# eth_part.net
KiCad netlist of a schematic drawn in Altium Designer
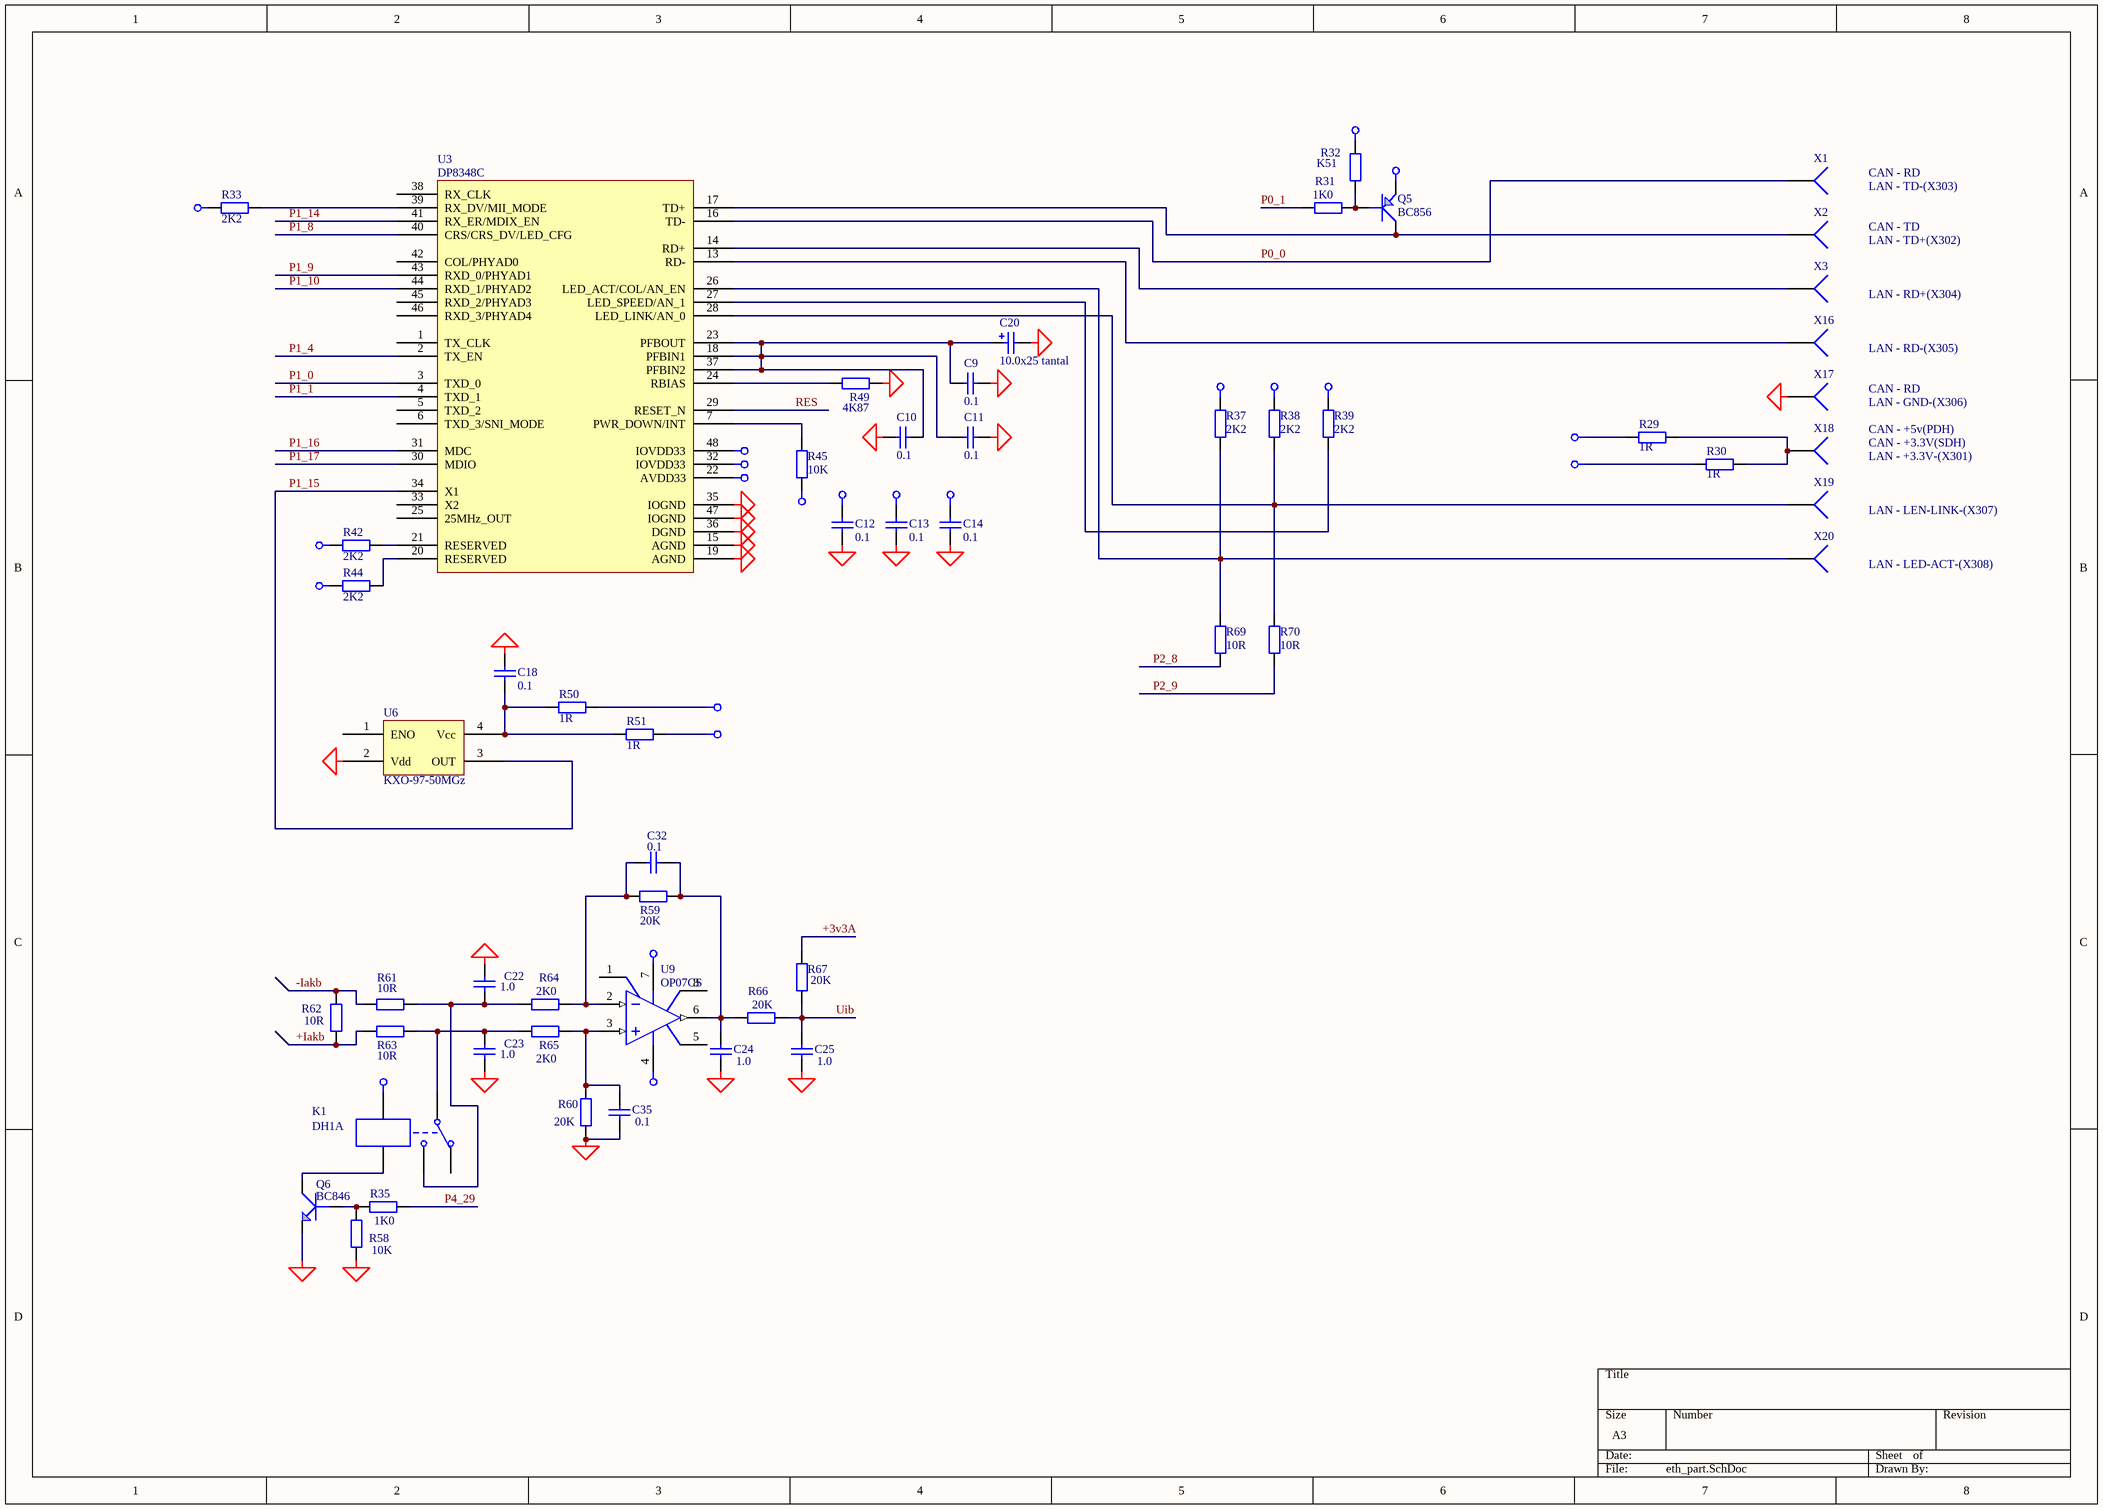
[diagram p0: eth_part.SchDoc]

(export (version "E")
  (design (tool "Eeschema 10.0.6"))
  (components
    (comp (ref "C9")
      (value "0.1")
      (footprint "C3216-1206")
      (description "Capacitor (Semiconductor SIM Model)")
      (fields (field (name "MANUFACTURER") "Generic Components") (field (name "PUBLISHER") "Altium Limited"))
      (libsource (lib "Miscellaneous Devices") (part "Cap Semi"))
    )
    (comp (ref "C10")
      (value "0.1")
      (footprint "C3216-1206")
      (description "Capacitor (Semiconductor SIM Model)")
      (fields (field (name "MANUFACTURER") "Generic Components") (field (name "PUBLISHER") "Altium Limited"))
      (libsource (lib "Miscellaneous Devices") (part "Cap Semi"))
    )
    (comp (ref "C11")
      (value "0.1")
      (footprint "C3216-1206")
      (description "Capacitor (Semiconductor SIM Model)")
      (fields (field (name "MANUFACTURER") "Generic Components") (field (name "PUBLISHER") "Altium Limited"))
      (libsource (lib "Miscellaneous Devices") (part "Cap Semi"))
    )
    (comp (ref "C12")
      (value "0.1")
      (footprint "_1206")
      (description "Capacitor (Semiconductor SIM Model)")
      (fields (field (name "MANUFACTURER") "Generic Components") (field (name "PUBLISHER") "Altium Limited"))
      (libsource (lib "Miscellaneous Devices") (part "Cap Semi"))
    )
    (comp (ref "C13")
      (value "0.1")
      (footprint "_1206")
      (description "Capacitor (Semiconductor SIM Model)")
      (fields (field (name "MANUFACTURER") "Generic Components") (field (name "PUBLISHER") "Altium Limited"))
      (libsource (lib "Miscellaneous Devices") (part "Cap Semi"))
    )
    (comp (ref "C14")
      (value "0.1")
      (footprint "_1206")
      (description "Capacitor (Semiconductor SIM Model)")
      (fields (field (name "MANUFACTURER") "Generic Components") (field (name "PUBLISHER") "Altium Limited"))
      (libsource (lib "Miscellaneous Devices") (part "Cap Semi"))
    )
    (comp (ref "C18")
      (value "0.1")
      (footprint "_1206")
      (description "Capacitor (Semiconductor SIM Model)")
      (fields (field (name "MANUFACTURER") "Generic Components") (field (name "PUBLISHER") "Altium Limited"))
      (libsource (lib "Miscellaneous Devices") (part "Cap Semi"))
    )
    (comp (ref "C20")
      (value "10.0x25 tantal")
      (footprint "CAP_EL_6_3")
      (description "Polarized Capacitor (Radial)")
      (fields (field (name "MANUFACTURER") "Generic Components") (field (name "PUBLISHER") "Altium Limited"))
      (libsource (lib "PAL") (part "Cap Pol1"))
    )
    (comp (ref "C22")
      (value "1.0")
      (footprint "_1206")
      (description "Capacitor (Semiconductor SIM Model)")
      (fields (field (name "MANUFACTURER") "Generic Components") (field (name "PUBLISHER") "Altium Limited"))
      (libsource (lib "Miscellaneous Devices") (part "Cap Semi"))
    )
    (comp (ref "C23")
      (value "1.0")
      (footprint "_1206")
      (description "Capacitor (Semiconductor SIM Model)")
      (fields (field (name "MANUFACTURER") "Generic Components") (field (name "PUBLISHER") "Altium Limited"))
      (libsource (lib "Miscellaneous Devices") (part "Cap Semi"))
    )
    (comp (ref "C24")
      (value "1.0")
      (footprint "_1206")
      (description "Capacitor (Semiconductor SIM Model)")
      (fields (field (name "MANUFACTURER") "Generic Components") (field (name "PUBLISHER") "Altium Limited"))
      (libsource (lib "Miscellaneous Devices") (part "Cap Semi"))
    )
    (comp (ref "C25")
      (value "1.0")
      (footprint "_1206")
      (description "Capacitor (Semiconductor SIM Model)")
      (fields (field (name "MANUFACTURER") "Generic Components") (field (name "PUBLISHER") "Altium Limited"))
      (libsource (lib "Miscellaneous Devices") (part "Cap Semi"))
    )
    (comp (ref "C32")
      (value "0.1")
      (footprint "_1206")
      (description "Capacitor (Semiconductor SIM Model)")
      (fields (field (name "MANUFACTURER") "Generic Components") (field (name "PUBLISHER") "Altium Limited"))
      (libsource (lib "Miscellaneous Devices") (part "Cap Semi"))
    )
    (comp (ref "C35")
      (value "0.1")
      (footprint "_1206")
      (description "Capacitor (Semiconductor SIM Model)")
      (fields (field (name "MANUFACTURER") "Generic Components") (field (name "PUBLISHER") "Altium Limited"))
      (libsource (lib "Miscellaneous Devices") (part "Cap Semi"))
    )
    (comp (ref "K1")
      (value "DH1A")
      (footprint "kuan")
      (description "Single-Pole Dual-Throw Relay")
      (fields (field (name "MANUFACTURER") "Generic Components") (field (name "PUBLISHER") "Altium Limited"))
      (libsource (lib "PAL") (part "BS115"))
    )
    (comp (ref "Q5") (value "BC856") (footprint "SO-G3") (libsource (lib "MAIN") (part "GT109")))
    (comp (ref "Q6") (value "BC846") (footprint "SO-G3") (libsource (lib "MAIN") (part "GT122")))
    (comp (ref "R29")
      (value "1R")
      (footprint "_1206")
      (description "Resistor")
      (fields (field (name "MANUFACTURER") "Generic Components") (field (name "PUBLISHER") "Altium Limited"))
      (libsource (lib "Miscellaneous Devices") (part "Res2"))
    )
    (comp (ref "R30")
      (value "1R")
      (footprint "_1206")
      (description "Resistor")
      (fields (field (name "MANUFACTURER") "Generic Components") (field (name "PUBLISHER") "Altium Limited"))
      (libsource (lib "Miscellaneous Devices") (part "Res2"))
    )
    (comp (ref "R31")
      (value "1K0")
      (footprint "_1206")
      (description "Resistor")
      (fields (field (name "MANUFACTURER") "Generic Components") (field (name "PUBLISHER") "Altium Limited"))
      (libsource (lib "") (part "Res2_3"))
    )
    (comp (ref "R32")
      (value "K51")
      (footprint "_1206")
      (description "Resistor")
      (fields (field (name "MANUFACTURER") "Generic Components") (field (name "PUBLISHER") "Altium Limited"))
      (libsource (lib "") (part "Res2_1"))
    )
    (comp (ref "R33")
      (value "2K2")
      (footprint "_1206")
      (description "Resistor")
      (fields (field (name "MANUFACTURER") "Generic Components") (field (name "PUBLISHER") "Altium Limited"))
      (libsource (lib "Miscellaneous Devices") (part "Res2"))
    )
    (comp (ref "R35")
      (value "1K0")
      (footprint "_1206")
      (description "Resistor")
      (fields (field (name "MANUFACTURER") "Generic Components") (field (name "PUBLISHER") "Altium Limited"))
      (libsource (lib "") (part "Res2_3"))
    )
    (comp (ref "R37")
      (value "2K2")
      (footprint "_1206")
      (description "Resistor")
      (fields (field (name "MANUFACTURER") "Generic Components") (field (name "PUBLISHER") "Altium Limited"))
      (libsource (lib "") (part "Res2_2"))
    )
    (comp (ref "R38")
      (value "2K2")
      (footprint "_1206")
      (description "Resistor")
      (fields (field (name "MANUFACTURER") "Generic Components") (field (name "PUBLISHER") "Altium Limited"))
      (libsource (lib "") (part "Res2_2"))
    )
    (comp (ref "R39")
      (value "2K2")
      (footprint "_1206")
      (description "Resistor")
      (fields (field (name "MANUFACTURER") "Generic Components") (field (name "PUBLISHER") "Altium Limited"))
      (libsource (lib "") (part "Res2_2"))
    )
    (comp (ref "R42")
      (value "2K2")
      (footprint "_1206")
      (description "Resistor")
      (fields (field (name "MANUFACTURER") "Generic Components") (field (name "PUBLISHER") "Altium Limited"))
      (libsource (lib "Miscellaneous Devices") (part "Res2"))
    )
    (comp (ref "R44")
      (value "2K2")
      (footprint "_1206")
      (description "Resistor")
      (fields (field (name "MANUFACTURER") "Generic Components") (field (name "PUBLISHER") "Altium Limited"))
      (libsource (lib "Miscellaneous Devices") (part "Res2"))
    )
    (comp (ref "R45")
      (value "10K")
      (footprint "_1206")
      (description "Resistor")
      (fields (field (name "MANUFACTURER") "Generic Components") (field (name "PUBLISHER") "Altium Limited"))
      (libsource (lib "") (part "Res2_3"))
    )
    (comp (ref "R49")
      (value "4K87")
      (footprint "_1206")
      (description "Resistor")
      (fields (field (name "MANUFACTURER") "Generic Components") (field (name "PUBLISHER") "Altium Limited"))
      (libsource (lib "Miscellaneous Devices") (part "Res2"))
    )
    (comp (ref "R50")
      (value "1R")
      (footprint "_1206")
      (description "Resistor")
      (fields (field (name "MANUFACTURER") "Generic Components") (field (name "PUBLISHER") "Altium Limited"))
      (libsource (lib "") (part "Res2_1"))
    )
    (comp (ref "R51")
      (value "1R")
      (footprint "_1206")
      (description "Resistor")
      (fields (field (name "MANUFACTURER") "Generic Components") (field (name "PUBLISHER") "Altium Limited"))
      (libsource (lib "") (part "Res2_1"))
    )
    (comp (ref "R58")
      (value "10K")
      (footprint "_1206")
      (description "Resistor")
      (fields (field (name "MANUFACTURER") "Generic Components") (field (name "PUBLISHER") "Altium Limited"))
      (libsource (lib "") (part "Res2_1"))
    )
    (comp (ref "R59")
      (value "20K")
      (footprint "_1206")
      (description "Resistor")
      (fields (field (name "MANUFACTURER") "Generic Components") (field (name "PUBLISHER") "Altium Limited"))
      (libsource (lib "Miscellaneous Devices") (part "Res2"))
    )
    (comp (ref "R60")
      (value "20K")
      (footprint "_1206")
      (description "Resistor")
      (fields (field (name "MANUFACTURER") "Generic Components") (field (name "PUBLISHER") "Altium Limited"))
      (libsource (lib "") (part "Res2_2"))
    )
    (comp (ref "R61")
      (value "10R")
      (footprint "_1206")
      (description "Resistor")
      (fields (field (name "MANUFACTURER") "Generic Components") (field (name "PUBLISHER") "Altium Limited"))
      (libsource (lib "Miscellaneous Devices") (part "Res2"))
    )
    (comp (ref "R62")
      (value "10R")
      (footprint "_1206")
      (description "Resistor")
      (fields (field (name "MANUFACTURER") "Generic Components") (field (name "PUBLISHER") "Altium Limited"))
      (libsource (lib "") (part "Res2_2"))
    )
    (comp (ref "R63")
      (value "10R")
      (footprint "_1206")
      (description "Resistor")
      (fields (field (name "MANUFACTURER") "Generic Components") (field (name "PUBLISHER") "Altium Limited"))
      (libsource (lib "Miscellaneous Devices") (part "Res2"))
    )
    (comp (ref "R64")
      (value "2K0")
      (footprint "_1206")
      (description "Resistor")
      (fields (field (name "MANUFACTURER") "Generic Components") (field (name "PUBLISHER") "Altium Limited"))
      (libsource (lib "") (part "Res2_1"))
    )
    (comp (ref "R65")
      (value "2K0")
      (footprint "_1206")
      (description "Resistor")
      (fields (field (name "MANUFACTURER") "Generic Components") (field (name "PUBLISHER") "Altium Limited"))
      (libsource (lib "") (part "Res2_1"))
    )
    (comp (ref "R66")
      (value "20K")
      (footprint "_1206")
      (description "Resistor")
      (fields (field (name "MANUFACTURER") "Generic Components") (field (name "PUBLISHER") "Altium Limited"))
      (libsource (lib "") (part "Res2_1"))
    )
    (comp (ref "R67")
      (value "20K")
      (footprint "_1206")
      (description "Resistor")
      (fields (field (name "MANUFACTURER") "Generic Components") (field (name "PUBLISHER") "Altium Limited"))
      (libsource (lib "") (part "Res2_1"))
    )
    (comp (ref "R69")
      (value "10R")
      (footprint "_1206")
      (description "Resistor")
      (fields (field (name "MANUFACTURER") "Generic Components") (field (name "PUBLISHER") "Altium Limited"))
      (libsource (lib "") (part "Res2_2"))
    )
    (comp (ref "R70")
      (value "10R")
      (footprint "_1206")
      (description "Resistor")
      (fields (field (name "MANUFACTURER") "Generic Components") (field (name "PUBLISHER") "Altium Limited"))
      (libsource (lib "") (part "Res2_2"))
    )
    (comp (ref "U3") (value "DP8348C") (footprint "F-QFP7X7-G48/N") (libsource (lib "PAL") (part "DP8348C")))
    (comp (ref "U6") (value "KXO-97-50MGz") (footprint "KXO-97") (libsource (lib "PAL") (part "KXO-97")))
    (comp (ref "U9")
      (value "OP07CS")
      (footprint "SO-G8")
      (description "Ultra-Low Offset Voltage Operational Amplifier")
      (fields (field (name "MANUFACTURER") "Analog Devices") (field (name "PUBLISHER") "Altium Limited"))
      (libsource (lib "AD Operational Amplifier") (part "OP07CS"))
    )
    (comp (ref "X1")
      (value "~")
      (footprint "PIN1")
      (description "Socket")
      (fields (field (name "MANUFACTURER") "Generic Components") (field (name "PUBLISHER") "Altium Limited"))
      (libsource (lib "Miscellaneous Connectors") (part "Socket"))
    )
    (comp (ref "X2")
      (value "~")
      (footprint "PIN1")
      (description "Socket")
      (fields (field (name "MANUFACTURER") "Generic Components") (field (name "PUBLISHER") "Altium Limited"))
      (libsource (lib "Miscellaneous Connectors") (part "Socket"))
    )
    (comp (ref "X3")
      (value "~")
      (footprint "PIN1")
      (description "Socket")
      (fields (field (name "MANUFACTURER") "Generic Components") (field (name "PUBLISHER") "Altium Limited"))
      (libsource (lib "Miscellaneous Connectors") (part "Socket"))
    )
    (comp (ref "X16")
      (value "~")
      (footprint "PIN1")
      (description "Socket")
      (fields (field (name "MANUFACTURER") "Generic Components") (field (name "PUBLISHER") "Altium Limited"))
      (libsource (lib "Miscellaneous Connectors") (part "Socket"))
    )
    (comp (ref "X17")
      (value "~")
      (footprint "PIN1")
      (description "Socket")
      (fields (field (name "MANUFACTURER") "Generic Components") (field (name "PUBLISHER") "Altium Limited"))
      (libsource (lib "Miscellaneous Connectors") (part "Socket"))
    )
    (comp (ref "X18")
      (value "~")
      (footprint "PIN1")
      (description "Socket")
      (fields (field (name "MANUFACTURER") "Generic Components") (field (name "PUBLISHER") "Altium Limited"))
      (libsource (lib "Miscellaneous Connectors") (part "Socket"))
    )
    (comp (ref "X19")
      (value "~")
      (footprint "PIN1")
      (description "Socket")
      (fields (field (name "MANUFACTURER") "Generic Components") (field (name "PUBLISHER") "Altium Limited"))
      (libsource (lib "Miscellaneous Connectors") (part "Socket"))
    )
    (comp (ref "X20")
      (value "~")
      (footprint "PIN1")
      (description "Socket")
      (fields (field (name "MANUFACTURER") "Generic Components") (field (name "PUBLISHER") "Altium Limited"))
      (libsource (lib "Miscellaneous Connectors") (part "Socket"))
    )
  )
  (nets
    (net (code "1") (name "+3v3") (class "Default")
      (node (ref "C12") (pin "1") (pinfunction "1_1") (pintype "passive"))
      (node (ref "C13") (pin "1") (pinfunction "1_1") (pintype "passive"))
      (node (ref "C14") (pin "1") (pinfunction "1_1") (pintype "passive"))
      (node (ref "Q5") (pin "2") (pinfunction "E_2") (pintype "passive"))
      (node (ref "R29") (pin "2") (pinfunction "2_2") (pintype "passive"))
      (node (ref "R32") (pin "2") (pinfunction "2_2") (pintype "passive"))
      (node (ref "R33") (pin "2") (pinfunction "2_2") (pintype "passive"))
      (node (ref "R37") (pin "2") (pinfunction "2_2") (pintype "passive"))
      (node (ref "R38") (pin "2") (pinfunction "2_2") (pintype "passive"))
      (node (ref "R39") (pin "2") (pinfunction "2_2") (pintype "passive"))
      (node (ref "R42") (pin "2") (pinfunction "2_2") (pintype "passive"))
      (node (ref "R44") (pin "2") (pinfunction "2_2") (pintype "passive"))
      (node (ref "R45") (pin "2") (pinfunction "2_2") (pintype "passive"))
      (node (ref "R51") (pin "2") (pinfunction "2_2") (pintype "passive"))
      (node (ref "U3") (pin "22") (pinfunction "AVDD33_22") (pintype "passive"))
      (node (ref "U3") (pin "32") (pinfunction "IOVDD33_32") (pintype "passive"))
      (node (ref "U3") (pin "48") (pinfunction "IOVDD33_48") (pintype "passive"))
    )
    (net (code "2") (name "+5v") (class "Default")
      (node (ref "K1") (pin "4") (pinfunction "4_4") (pintype "passive"))
      (node (ref "R30") (pin "2") (pinfunction "2_2") (pintype "passive"))
      (node (ref "R50") (pin "2") (pinfunction "2_2") (pintype "passive"))
      (node (ref "U9") (pin "7") (pinfunction "V+_7") (pintype "power_in"))
    )
    (net (code "3") (name "-5v") (class "Default")
      (node (ref "U9") (pin "4") (pinfunction "V-_4") (pintype "power_in"))
    )
    (net (code "4") (name "/+3v3A") (class "Default")
      (node (ref "R67") (pin "2") (pinfunction "2_2") (pintype "passive"))
    )
    (net (code "5") (name "/+Iakb") (class "Default")
      (node (ref "R62") (pin "1") (pinfunction "1_1") (pintype "passive"))
      (node (ref "R63") (pin "2") (pinfunction "2_2") (pintype "passive"))
    )
    (net (code "6") (name "/-Iakb") (class "Default")
      (node (ref "R61") (pin "2") (pinfunction "2_2") (pintype "passive"))
      (node (ref "R62") (pin "2") (pinfunction "2_2") (pintype "passive"))
    )
    (net (code "7") (name "/P0_0") (class "Default")
      (node (ref "U3") (pin "16") (pinfunction "TD-_16") (pintype "passive"))
      (node (ref "X1") (pin "1") (pinfunction "1_1") (pintype "passive"))
    )
    (net (code "8") (name "/P0_1") (class "Default")
      (node (ref "R31") (pin "2") (pinfunction "2_2") (pintype "passive"))
    )
    (net (code "9") (name "/P1_0") (class "Default")
      (node (ref "U3") (pin "3") (pinfunction "TXD_0_3") (pintype "passive"))
    )
    (net (code "10") (name "/P1_1") (class "Default")
      (node (ref "U3") (pin "4") (pinfunction "TXD_1_4") (pintype "passive"))
    )
    (net (code "11") (name "/P1_4") (class "Default")
      (node (ref "U3") (pin "2") (pinfunction "TX_EN_2") (pintype "passive"))
    )
    (net (code "12") (name "/P1_8") (class "Default")
      (node (ref "U3") (pin "40") (pinfunction "CRS/CRS_DV/LED_CFG_40") (pintype "passive"))
    )
    (net (code "13") (name "/P1_9") (class "Default")
      (node (ref "U3") (pin "43") (pinfunction "RXD_0/PHYAD1_43") (pintype "passive"))
    )
    (net (code "14") (name "/P1_10") (class "Default")
      (node (ref "U3") (pin "44") (pinfunction "RXD_1/PHYAD2_44") (pintype "passive"))
    )
    (net (code "15") (name "/P1_14") (class "Default")
      (node (ref "U3") (pin "41") (pinfunction "RX_ER/MDIX_EN_41") (pintype "passive"))
    )
    (net (code "16") (name "/P1_15") (class "Default")
      (node (ref "U3") (pin "34") (pinfunction "X1_34") (pintype "passive"))
      (node (ref "U6") (pin "3") (pinfunction "OUT_3") (pintype "passive"))
    )
    (net (code "17") (name "/P1_16") (class "Default")
      (node (ref "U3") (pin "31") (pinfunction "MDC_31") (pintype "passive"))
    )
    (net (code "18") (name "/P1_17") (class "Default")
      (node (ref "U3") (pin "30") (pinfunction "MDIO_30") (pintype "passive"))
    )
    (net (code "19") (name "/P2_8") (class "Default")
      (node (ref "R69") (pin "1") (pinfunction "1_1") (pintype "passive"))
    )
    (net (code "20") (name "/P2_9") (class "Default")
      (node (ref "R70") (pin "1") (pinfunction "1_1") (pintype "passive"))
    )
    (net (code "21") (name "/P4_29") (class "Default")
      (node (ref "R35") (pin "1") (pinfunction "1_1") (pintype "passive"))
    )
    (net (code "22") (name "/RES") (class "Default")
      (node (ref "U3") (pin "29") (pinfunction "RESET_N_29") (pintype "passive"))
    )
    (net (code "23") (name "/Uib") (class "Default")
      (node (ref "C25") (pin "2") (pinfunction "2_2") (pintype "passive"))
      (node (ref "R66") (pin "2") (pinfunction "2_2") (pintype "passive"))
      (node (ref "R67") (pin "1") (pinfunction "1_1") (pintype "passive"))
    )
    (net (code "24") (name "GND") (class "Default")
      (node (ref "C10") (pin "2") (pinfunction "2_2") (pintype "passive"))
      (node (ref "C11") (pin "2") (pinfunction "2_2") (pintype "passive"))
      (node (ref "C12") (pin "2") (pinfunction "2_2") (pintype "passive"))
      (node (ref "C13") (pin "2") (pinfunction "2_2") (pintype "passive"))
      (node (ref "C14") (pin "2") (pinfunction "2_2") (pintype "passive"))
      (node (ref "C18") (pin "2") (pinfunction "2_2") (pintype "passive"))
      (node (ref "C20") (pin "2") (pinfunction "2_2") (pintype "passive"))
      (node (ref "C22") (pin "1") (pinfunction "1_1") (pintype "passive"))
      (node (ref "C23") (pin "2") (pinfunction "2_2") (pintype "passive"))
      (node (ref "C24") (pin "1") (pinfunction "1_1") (pintype "passive"))
      (node (ref "C25") (pin "1") (pinfunction "1_1") (pintype "passive"))
      (node (ref "C35") (pin "2") (pinfunction "2_2") (pintype "passive"))
      (node (ref "C9") (pin "2") (pinfunction "2_2") (pintype "passive"))
      (node (ref "Q6") (pin "2") (pinfunction "E_2") (pintype "passive"))
      (node (ref "R49") (pin "1") (pinfunction "1_1") (pintype "passive"))
      (node (ref "R58") (pin "1") (pinfunction "1_1") (pintype "passive"))
      (node (ref "R60") (pin "1") (pinfunction "1_1") (pintype "passive"))
      (node (ref "U3") (pin "15") (pinfunction "AGND_15") (pintype "passive"))
      (node (ref "U3") (pin "19") (pinfunction "AGND_19") (pintype "passive"))
      (node (ref "U3") (pin "35") (pinfunction "IOGND_35") (pintype "passive"))
      (node (ref "U3") (pin "36") (pinfunction "DGND_36") (pintype "passive"))
      (node (ref "U3") (pin "47") (pinfunction "IOGND_47") (pintype "passive"))
      (node (ref "U6") (pin "2") (pinfunction "Vdd_2") (pintype "passive"))
      (node (ref "X17") (pin "1") (pinfunction "1_1") (pintype "passive"))
    )
    (net (code "25") (name "Net-(C22-Pad2)") (class "Default")
      (node (ref "C22") (pin "2") (pinfunction "2_2") (pintype "passive"))
      (node (ref "K1") (pin "3") (pinfunction "3_3") (pintype "passive"))
      (node (ref "R61") (pin "1") (pinfunction "1_1") (pintype "passive"))
      (node (ref "R64") (pin "1") (pinfunction "1_1") (pintype "passive"))
    )
    (net (code "26") (name "Net-(C23-Pad1)") (class "Default")
      (node (ref "C23") (pin "1") (pinfunction "1_1") (pintype "passive"))
      (node (ref "K1") (pin "1") (pinfunction "1_1") (pintype "passive"))
      (node (ref "R63") (pin "1") (pinfunction "1_1") (pintype "passive"))
      (node (ref "R65") (pin "1") (pinfunction "1_1") (pintype "passive"))
    )
    (net (code "27") (name "Net-(Q5-B)") (class "Default")
      (node (ref "Q5") (pin "1") (pinfunction "B_1") (pintype "passive"))
      (node (ref "R31") (pin "1") (pinfunction "1_1") (pintype "passive"))
      (node (ref "R32") (pin "1") (pinfunction "1_1") (pintype "passive"))
    )
    (net (code "28") (name "Net-(Q5-C)") (class "Default")
      (node (ref "Q5") (pin "3") (pinfunction "C_3") (pintype "passive"))
      (node (ref "U3") (pin "17") (pinfunction "TD+_17") (pintype "passive"))
      (node (ref "X2") (pin "1") (pinfunction "1_1") (pintype "passive"))
    )
    (net (code "29") (name "Net-(Q6-B)") (class "Default")
      (node (ref "Q6") (pin "1") (pinfunction "B_1") (pintype "passive"))
      (node (ref "R35") (pin "2") (pinfunction "2_2") (pintype "passive"))
      (node (ref "R58") (pin "2") (pinfunction "2_2") (pintype "passive"))
    )
    (net (code "30") (name "Net-(Q6-C)") (class "Default")
      (node (ref "K1") (pin "5") (pinfunction "5_5") (pintype "passive"))
      (node (ref "Q6") (pin "3") (pinfunction "C_3") (pintype "passive"))
    )
    (net (code "31") (name "Net-(R29-Pad1)") (class "Default")
      (node (ref "R29") (pin "1") (pinfunction "1_1") (pintype "passive"))
      (node (ref "R30") (pin "1") (pinfunction "1_1") (pintype "passive"))
      (node (ref "X18") (pin "1") (pinfunction "1_1") (pintype "passive"))
    )
    (net (code "32") (name "Net-(R42-Pad1)") (class "Default")
      (node (ref "R42") (pin "1") (pinfunction "1_1") (pintype "passive"))
      (node (ref "U3") (pin "21") (pinfunction "RESERVED_21") (pintype "passive"))
    )
    (net (code "33") (name "Net-(R44-Pad1)") (class "Default")
      (node (ref "R44") (pin "1") (pinfunction "1_1") (pintype "passive"))
      (node (ref "U3") (pin "20") (pinfunction "RESERVED_20") (pintype "passive"))
    )
    (net (code "34") (name "Net-(U3-LED_ACT{slash}COL{slash}AN_EN)") (class "Default")
      (node (ref "R37") (pin "1") (pinfunction "1_1") (pintype "passive"))
      (node (ref "R69") (pin "2") (pinfunction "2_2") (pintype "passive"))
      (node (ref "U3") (pin "26") (pinfunction "LED_ACT/COL/AN_EN_26") (pintype "passive"))
      (node (ref "X20") (pin "1") (pinfunction "1_1") (pintype "passive"))
    )
    (net (code "35") (name "Net-(U3-LED_LINK{slash}AN_0)") (class "Default")
      (node (ref "R38") (pin "1") (pinfunction "1_1") (pintype "passive"))
      (node (ref "R70") (pin "2") (pinfunction "2_2") (pintype "passive"))
      (node (ref "U3") (pin "28") (pinfunction "LED_LINK/AN_0_28") (pintype "passive"))
      (node (ref "X19") (pin "1") (pinfunction "1_1") (pintype "passive"))
    )
    (net (code "36") (name "Net-(U3-LED_SPEED{slash}AN_1)") (class "Default")
      (node (ref "R39") (pin "1") (pinfunction "1_1") (pintype "passive"))
      (node (ref "U3") (pin "27") (pinfunction "LED_SPEED/AN_1_27") (pintype "passive"))
    )
    (net (code "37") (name "Net-(U3-PFBIN1)") (class "Default")
      (node (ref "C10") (pin "1") (pinfunction "1_1") (pintype "passive"))
      (node (ref "C11") (pin "1") (pinfunction "1_1") (pintype "passive"))
      (node (ref "C20") (pin "1") (pinfunction "1_1") (pintype "passive"))
      (node (ref "C9") (pin "1") (pinfunction "1_1") (pintype "passive"))
      (node (ref "U3") (pin "18") (pinfunction "PFBIN1_18") (pintype "passive"))
      (node (ref "U3") (pin "23") (pinfunction "PFBOUT_23") (pintype "passive"))
      (node (ref "U3") (pin "37") (pinfunction "PFBIN2_37") (pintype "passive"))
    )
    (net (code "38") (name "Net-(U3-PWR_DOWN{slash}INT)") (class "Default")
      (node (ref "R45") (pin "1") (pinfunction "1_1") (pintype "passive"))
      (node (ref "U3") (pin "7") (pinfunction "PWR_DOWN/INT_7") (pintype "passive"))
    )
    (net (code "39") (name "Net-(U3-RBIAS)") (class "Default")
      (node (ref "R49") (pin "2") (pinfunction "2_2") (pintype "passive"))
      (node (ref "U3") (pin "24") (pinfunction "RBIAS_24") (pintype "passive"))
    )
    (net (code "40") (name "Net-(U3-RD+)") (class "Default")
      (node (ref "U3") (pin "14") (pinfunction "RD+_14") (pintype "passive"))
      (node (ref "X3") (pin "1") (pinfunction "1_1") (pintype "passive"))
    )
    (net (code "41") (name "Net-(U3-RD-)") (class "Default")
      (node (ref "U3") (pin "13") (pinfunction "RD-_13") (pintype "passive"))
      (node (ref "X16") (pin "1") (pinfunction "1_1") (pintype "passive"))
    )
    (net (code "42") (name "Net-(U3-RX_DV{slash}MII_MODE)") (class "Default")
      (node (ref "R33") (pin "1") (pinfunction "1_1") (pintype "passive"))
      (node (ref "U3") (pin "39") (pinfunction "RX_DV/MII_MODE_39") (pintype "passive"))
    )
    (net (code "43") (name "Net-(U6-Vcc)") (class "Default")
      (node (ref "C18") (pin "1") (pinfunction "1_1") (pintype "passive"))
      (node (ref "R50") (pin "1") (pinfunction "1_1") (pintype "passive"))
      (node (ref "R51") (pin "1") (pinfunction "1_1") (pintype "passive"))
      (node (ref "U6") (pin "4") (pinfunction "Vcc_4") (pintype "passive"))
    )
    (net (code "44") (name "Net-(U9-IN+)") (class "Default")
      (node (ref "C35") (pin "1") (pinfunction "1_1") (pintype "passive"))
      (node (ref "R60") (pin "2") (pinfunction "2_2") (pintype "passive"))
      (node (ref "R65") (pin "2") (pinfunction "2_2") (pintype "passive"))
      (node (ref "U9") (pin "3") (pinfunction "IN+_3") (pintype "input"))
    )
    (net (code "45") (name "Net-(U9-IN-)") (class "Default")
      (node (ref "C32") (pin "1") (pinfunction "1_1") (pintype "passive"))
      (node (ref "R59") (pin "2") (pinfunction "2_2") (pintype "passive"))
      (node (ref "R64") (pin "2") (pinfunction "2_2") (pintype "passive"))
      (node (ref "U9") (pin "2") (pinfunction "IN-_2") (pintype "input"))
    )
    (net (code "46") (name "Net-(U9-OUT)") (class "Default")
      (node (ref "C24") (pin "2") (pinfunction "2_2") (pintype "passive"))
      (node (ref "C32") (pin "2") (pinfunction "2_2") (pintype "passive"))
      (node (ref "R59") (pin "1") (pinfunction "1_1") (pintype "passive"))
      (node (ref "R66") (pin "1") (pinfunction "1_1") (pintype "passive"))
      (node (ref "U9") (pin "6") (pinfunction "OUT_6") (pintype "output"))
    )
    (net (code "47") (name "unconnected-(K1-Pad2)") (class "Default")
      (node (ref "K1") (pin "2") (pinfunction "2_2") (pintype "passive"))
    )
    (net (code "48") (name "unconnected-(U3-25MHz_OUT-Pad25)") (class "Default")
      (node (ref "U3") (pin "25") (pinfunction "25MHz_OUT_25") (pintype "passive"))
    )
    (net (code "49") (name "unconnected-(U3-COL{slash}PHYAD0-Pad42)") (class "Default")
      (node (ref "U3") (pin "42") (pinfunction "COL/PHYAD0_42") (pintype "passive"))
    )
    (net (code "50") (name "unconnected-(U3-RXD_2{slash}PHYAD3-Pad45)") (class "Default")
      (node (ref "U3") (pin "45") (pinfunction "RXD_2/PHYAD3_45") (pintype "passive"))
    )
    (net (code "51") (name "unconnected-(U3-RXD_3{slash}PHYAD4-Pad46)") (class "Default")
      (node (ref "U3") (pin "46") (pinfunction "RXD_3/PHYAD4_46") (pintype "passive"))
    )
    (net (code "52") (name "unconnected-(U3-RX_CLK-Pad38)") (class "Default")
      (node (ref "U3") (pin "38") (pinfunction "RX_CLK_38") (pintype "passive"))
    )
    (net (code "53") (name "unconnected-(U3-TXD_2-Pad5)") (class "Default")
      (node (ref "U3") (pin "5") (pinfunction "TXD_2_5") (pintype "passive"))
    )
    (net (code "54") (name "unconnected-(U3-TXD_3{slash}SNI_MODE-Pad6)") (class "Default")
      (node (ref "U3") (pin "6") (pinfunction "TXD_3/SNI_MODE_6") (pintype "passive"))
    )
    (net (code "55") (name "unconnected-(U3-TX_CLK-Pad1)") (class "Default")
      (node (ref "U3") (pin "1") (pinfunction "TX_CLK_1") (pintype "passive"))
    )
    (net (code "56") (name "unconnected-(U3-X2-Pad33)") (class "Default")
      (node (ref "U3") (pin "33") (pinfunction "X2_33") (pintype "passive"))
    )
    (net (code "57") (name "unconnected-(U6-ENO-Pad1)") (class "Default")
      (node (ref "U6") (pin "1") (pinfunction "ENO_1") (pintype "passive"))
    )
    (net (code "58") (name "unconnected-(U9-NC-Pad5)") (class "Default")
      (node (ref "U9") (pin "5") (pinfunction "NC_5") (pintype "passive"))
    )
    (net (code "59") (name "unconnected-(U9-VOSTRIM-Pad1)") (class "Default")
      (node (ref "U9") (pin "1") (pinfunction "VOSTRIM_1") (pintype "passive"))
    )
    (net (code "60") (name "unconnected-(U9-VOSTRIM-Pad8)") (class "Default")
      (node (ref "U9") (pin "8") (pinfunction "VOSTRIM_8") (pintype "passive"))
    )
  )
)
